# top.net
KiCad netlist of a schematic drawn in Altium Designer
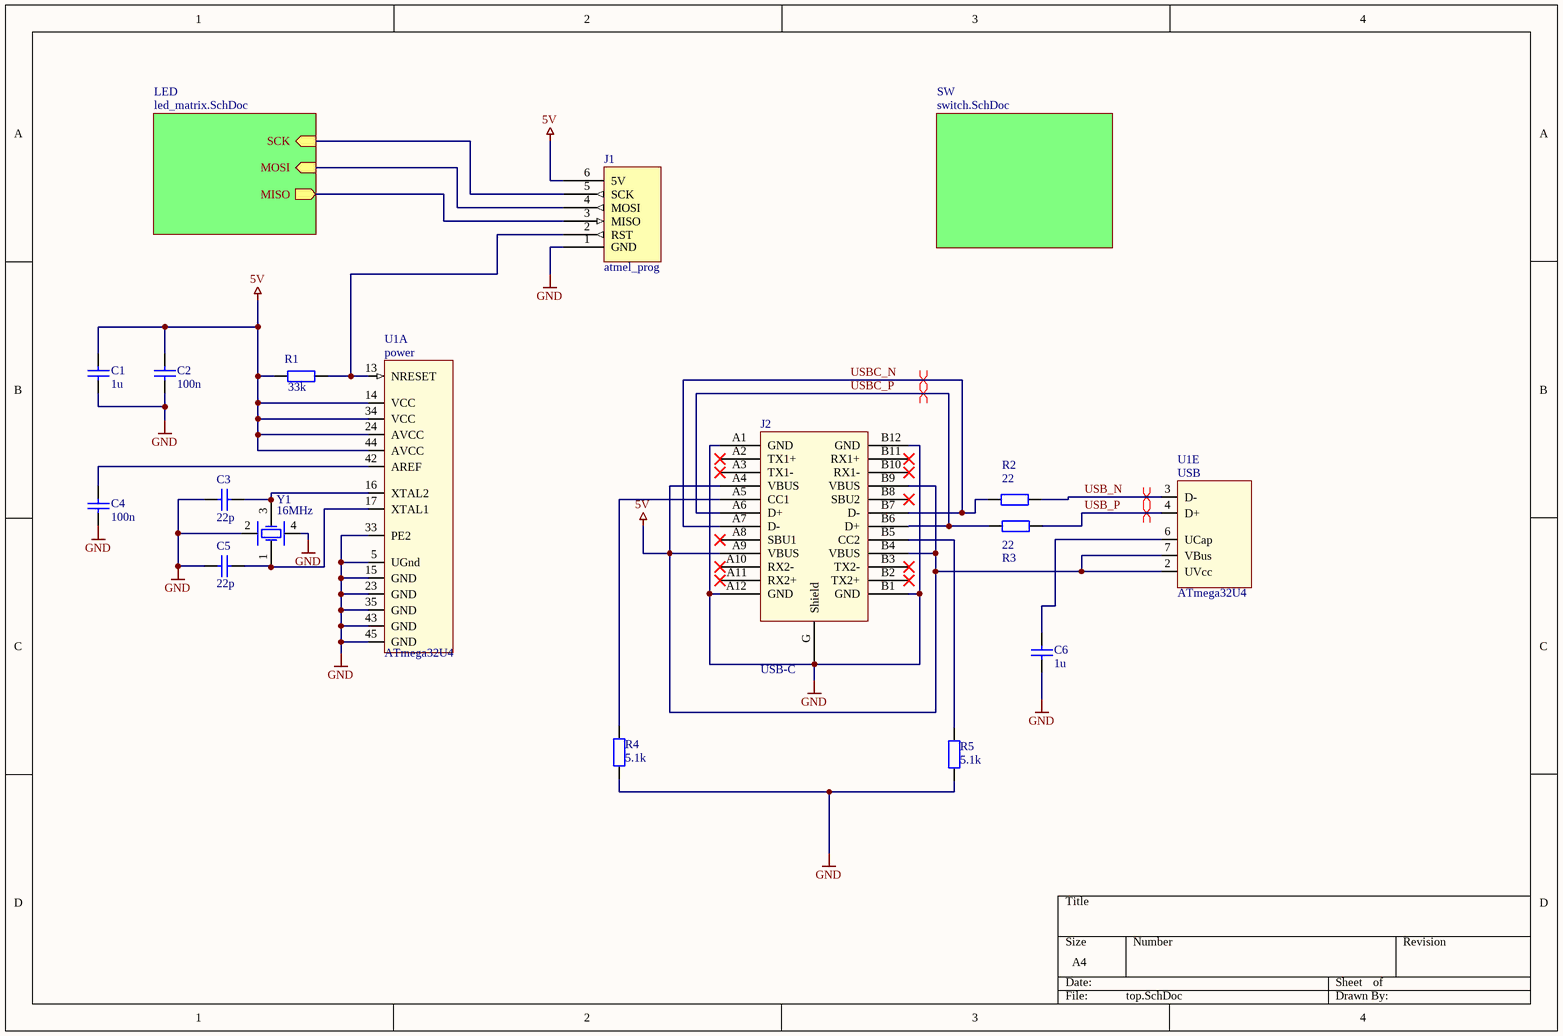
[diagram p0: top.SchDoc]

(export (version "E")
  (design (tool "Eeschema 10.0.6"))
  (components
    (comp (ref "C1") (value "1u") (footprint "0805") (libsource (lib "generic_components") (part "cap")))
    (comp (ref "C2") (value "100n") (footprint "0805") (libsource (lib "generic_components") (part "cap")))
    (comp (ref "C3") (value "22p") (footprint "0805") (libsource (lib "generic_components") (part "cap")))
    (comp (ref "C4") (value "100n") (footprint "0805") (libsource (lib "generic_components") (part "cap")))
    (comp (ref "C5") (value "22p") (footprint "0805") (libsource (lib "generic_components") (part "cap")))
    (comp (ref "C6") (value "1u") (footprint "0805") (libsource (lib "generic_components") (part "cap")))
    (comp (ref "J1")
      (value "atmel_prog")
      (footprint "header6p0.2")
      (libsource (lib "generic_conn") (part "atmel_prog"))
    )
    (comp (ref "J2") (value "USB-C") (footprint "usb-c") (libsource (lib "JST") (part "USB-C")))
    (comp (ref "R1") (value "33k") (footprint "0805") (libsource (lib "") (part "res0805_1")))
    (comp (ref "R2") (value "22") (footprint "0805") (libsource (lib "") (part "res0805_1")))
    (comp (ref "R3") (value "22") (footprint "0805") (libsource (lib "") (part "res0805_1")))
    (comp (ref "R4")
      (value "5.1k")
      (footprint "0805")
      (libsource (lib "generic_components") (part "res0805"))
    )
    (comp (ref "R5")
      (value "5.1k")
      (footprint "0805")
      (libsource (lib "generic_components") (part "res0805"))
    )
    (comp (ref "U1")
      (value "ATmega32U4")
      (footprint "QFN44P05P7X7")
      (libsource (lib "atmel") (part "ATmega32U4"))
    )
    (comp (ref "Y1")
      (value "16MHz")
      (footprint "SMD_crystal_P220x160S320x250")
      (libsource (lib "generic_components") (part "xtal"))
    )
  )
  (nets
    (net (code "1") (name "/MISO") (class "Default")
      (node (ref "J1") (pin "3") (pinfunction "MISO_3") (pintype "input"))
    )
    (net (code "2") (name "/MOSI") (class "Default")
      (node (ref "J1") (pin "4") (pinfunction "MOSI_4") (pintype "output"))
    )
    (net (code "3") (name "/SCK") (class "Default")
      (node (ref "J1") (pin "5") (pinfunction "SCK_5") (pintype "output"))
    )
    (net (code "4") (name "/USBC_N") (class "Default")
      (node (ref "J2") (pin "A7") (pinfunction "D-_A7") (pintype "passive"))
      (node (ref "J2") (pin "B7") (pinfunction "D-_B7") (pintype "passive"))
      (node (ref "R2") (pin "1") (pintype "passive"))
    )
    (net (code "5") (name "/USBC_P") (class "Default")
      (node (ref "J2") (pin "A6") (pinfunction "D+_A6") (pintype "passive"))
      (node (ref "J2") (pin "B6") (pinfunction "D+_B6") (pintype "passive"))
      (node (ref "R3") (pin "1") (pintype "passive"))
    )
    (net (code "6") (name "/USB_N") (class "Default")
      (node (ref "R2") (pin "2") (pinfunction "2_2") (pintype "passive"))
      (node (ref "U1") (pin "3") (pinfunction "D-_3") (pintype "bidirectional"))
    )
    (net (code "7") (name "/USB_P") (class "Default")
      (node (ref "R3") (pin "2") (pinfunction "2_2") (pintype "passive"))
      (node (ref "U1") (pin "4") (pinfunction "D+_4") (pintype "bidirectional"))
    )
    (net (code "8") (name "5V") (class "Default")
      (node (ref "C1") (pin "2") (pinfunction "2_2") (pintype "passive"))
      (node (ref "C2") (pin "2") (pinfunction "2_2") (pintype "passive"))
      (node (ref "J1") (pin "6") (pinfunction "5V_6") (pintype "power_in"))
      (node (ref "J2") (pin "A4") (pinfunction "VBUS_A4") (pintype "passive"))
      (node (ref "J2") (pin "A9") (pinfunction "VBUS_A9") (pintype "passive"))
      (node (ref "J2") (pin "B4") (pinfunction "VBUS_B4") (pintype "passive"))
      (node (ref "J2") (pin "B9") (pinfunction "VBUS_B9") (pintype "passive"))
      (node (ref "R1") (pin "1") (pintype "passive"))
      (node (ref "U1") (pin "14") (pinfunction "VCC_14") (pintype "passive"))
      (node (ref "U1") (pin "2") (pinfunction "UVcc_2") (pintype "passive"))
      (node (ref "U1") (pin "24") (pinfunction "AVCC_24") (pintype "passive"))
      (node (ref "U1") (pin "34") (pinfunction "VCC_34") (pintype "passive"))
      (node (ref "U1") (pin "44") (pinfunction "AVCC_44") (pintype "passive"))
      (node (ref "U1") (pin "7") (pinfunction "VBus_7") (pintype "passive"))
    )
    (net (code "9") (name "GND") (class "Default")
      (node (ref "C1") (pin "1") (pinfunction "1_1") (pintype "passive"))
      (node (ref "C2") (pin "1") (pinfunction "1_1") (pintype "passive"))
      (node (ref "C3") (pin "2") (pinfunction "2_2") (pintype "passive"))
      (node (ref "C4") (pin "1") (pinfunction "1_1") (pintype "passive"))
      (node (ref "C5") (pin "2") (pinfunction "2_2") (pintype "passive"))
      (node (ref "C6") (pin "1") (pinfunction "1_1") (pintype "passive"))
      (node (ref "J1") (pin "1") (pinfunction "GND_1") (pintype "power_in"))
      (node (ref "J2") (pin "A1") (pinfunction "GND_A1") (pintype "passive"))
      (node (ref "J2") (pin "A12") (pinfunction "GND_A12") (pintype "passive"))
      (node (ref "J2") (pin "B1") (pinfunction "GND_B1") (pintype "passive"))
      (node (ref "J2") (pin "B12") (pinfunction "GND_B12") (pintype "passive"))
      (node (ref "J2") (pin "G") (pinfunction "Shield_G") (pintype "passive"))
      (node (ref "R4") (pin "2") (pinfunction "2_2") (pintype "passive"))
      (node (ref "R5") (pin "2") (pinfunction "2_2") (pintype "passive"))
      (node (ref "U1") (pin "15") (pinfunction "GND_15") (pintype "passive"))
      (node (ref "U1") (pin "23") (pinfunction "GND_23") (pintype "passive"))
      (node (ref "U1") (pin "33") (pinfunction "PE2_33") (pintype "bidirectional"))
      (node (ref "U1") (pin "35") (pinfunction "GND_35") (pintype "passive"))
      (node (ref "U1") (pin "43") (pinfunction "GND_43") (pintype "passive"))
      (node (ref "U1") (pin "45") (pinfunction "GND_45") (pintype "passive"))
      (node (ref "U1") (pin "5") (pinfunction "UGnd_5") (pintype "passive"))
      (node (ref "Y1") (pin "2") (pinfunction "2_2") (pintype "passive"))
      (node (ref "Y1") (pin "4") (pinfunction "4_4") (pintype "passive"))
    )
    (net (code "10") (name "Net-(J1-RST)") (class "Default")
      (node (ref "J1") (pin "2") (pinfunction "RST_2") (pintype "output"))
      (node (ref "R1") (pin "2") (pinfunction "2_2") (pintype "passive"))
      (node (ref "U1") (pin "13") (pinfunction "NRESET_13") (pintype "input"))
    )
    (net (code "11") (name "Net-(J2-CC1)") (class "Default")
      (node (ref "J2") (pin "A5") (pinfunction "CC1_A5") (pintype "passive"))
      (node (ref "R4") (pin "1") (pintype "passive"))
    )
    (net (code "12") (name "Net-(J2-CC2)") (class "Default")
      (node (ref "J2") (pin "B5") (pinfunction "CC2_B5") (pintype "passive"))
      (node (ref "R5") (pin "1") (pintype "passive"))
    )
    (net (code "13") (name "Net-(U1A-AREF)") (class "Default")
      (node (ref "C4") (pin "2") (pinfunction "2_2") (pintype "passive"))
      (node (ref "U1") (pin "42") (pinfunction "AREF_42") (pintype "passive"))
    )
    (net (code "14") (name "Net-(U1A-XTAL1)") (class "Default")
      (node (ref "C5") (pin "1") (pinfunction "1_1") (pintype "passive"))
      (node (ref "U1") (pin "17") (pinfunction "XTAL1_17") (pintype "passive"))
      (node (ref "Y1") (pin "1") (pinfunction "OSC1_1") (pintype "passive"))
    )
    (net (code "15") (name "Net-(U1A-XTAL2)") (class "Default")
      (node (ref "C3") (pin "1") (pinfunction "1_1") (pintype "passive"))
      (node (ref "U1") (pin "16") (pinfunction "XTAL2_16") (pintype "passive"))
      (node (ref "Y1") (pin "3") (pinfunction "OSC2_3") (pintype "passive"))
    )
    (net (code "16") (name "Net-(U1E-UCap)") (class "Default")
      (node (ref "C6") (pin "2") (pinfunction "2_2") (pintype "passive"))
      (node (ref "U1") (pin "6") (pinfunction "UCap_6") (pintype "passive"))
    )
    (net (code "17") (name "unconnected-(J2-RX1+-PadB11)") (class "Default")
      (node (ref "J2") (pin "B11") (pinfunction "RX1+_B11") (pintype "passive+no_connect"))
    )
    (net (code "18") (name "unconnected-(J2-RX1--PadB10)") (class "Default")
      (node (ref "J2") (pin "B10") (pinfunction "RX1-_B10") (pintype "passive+no_connect"))
    )
    (net (code "19") (name "unconnected-(J2-RX2+-PadA11)") (class "Default")
      (node (ref "J2") (pin "A11") (pinfunction "RX2+_A11") (pintype "passive+no_connect"))
    )
    (net (code "20") (name "unconnected-(J2-RX2--PadA10)") (class "Default")
      (node (ref "J2") (pin "A10") (pinfunction "RX2-_A10") (pintype "passive+no_connect"))
    )
    (net (code "21") (name "unconnected-(J2-SBU1-PadA8)") (class "Default")
      (node (ref "J2") (pin "A8") (pinfunction "SBU1_A8") (pintype "passive+no_connect"))
    )
    (net (code "22") (name "unconnected-(J2-SBU2-PadB8)") (class "Default")
      (node (ref "J2") (pin "B8") (pinfunction "SBU2_B8") (pintype "passive+no_connect"))
    )
    (net (code "23") (name "unconnected-(J2-TX1+-PadA2)") (class "Default")
      (node (ref "J2") (pin "A2") (pinfunction "TX1+_A2") (pintype "passive+no_connect"))
    )
    (net (code "24") (name "unconnected-(J2-TX1--PadA3)") (class "Default")
      (node (ref "J2") (pin "A3") (pinfunction "TX1-_A3") (pintype "passive+no_connect"))
    )
    (net (code "25") (name "unconnected-(J2-TX2+-PadB2)") (class "Default")
      (node (ref "J2") (pin "B2") (pinfunction "TX2+_B2") (pintype "passive+no_connect"))
    )
    (net (code "26") (name "unconnected-(J2-TX2--PadB3)") (class "Default")
      (node (ref "J2") (pin "B3") (pinfunction "TX2-_B3") (pintype "passive+no_connect"))
    )
  )
)
